# ProPrj_flap_controller_v2_2024-11-15.net
KiCad netlist of a schematic drawn in EasyEDA Pro
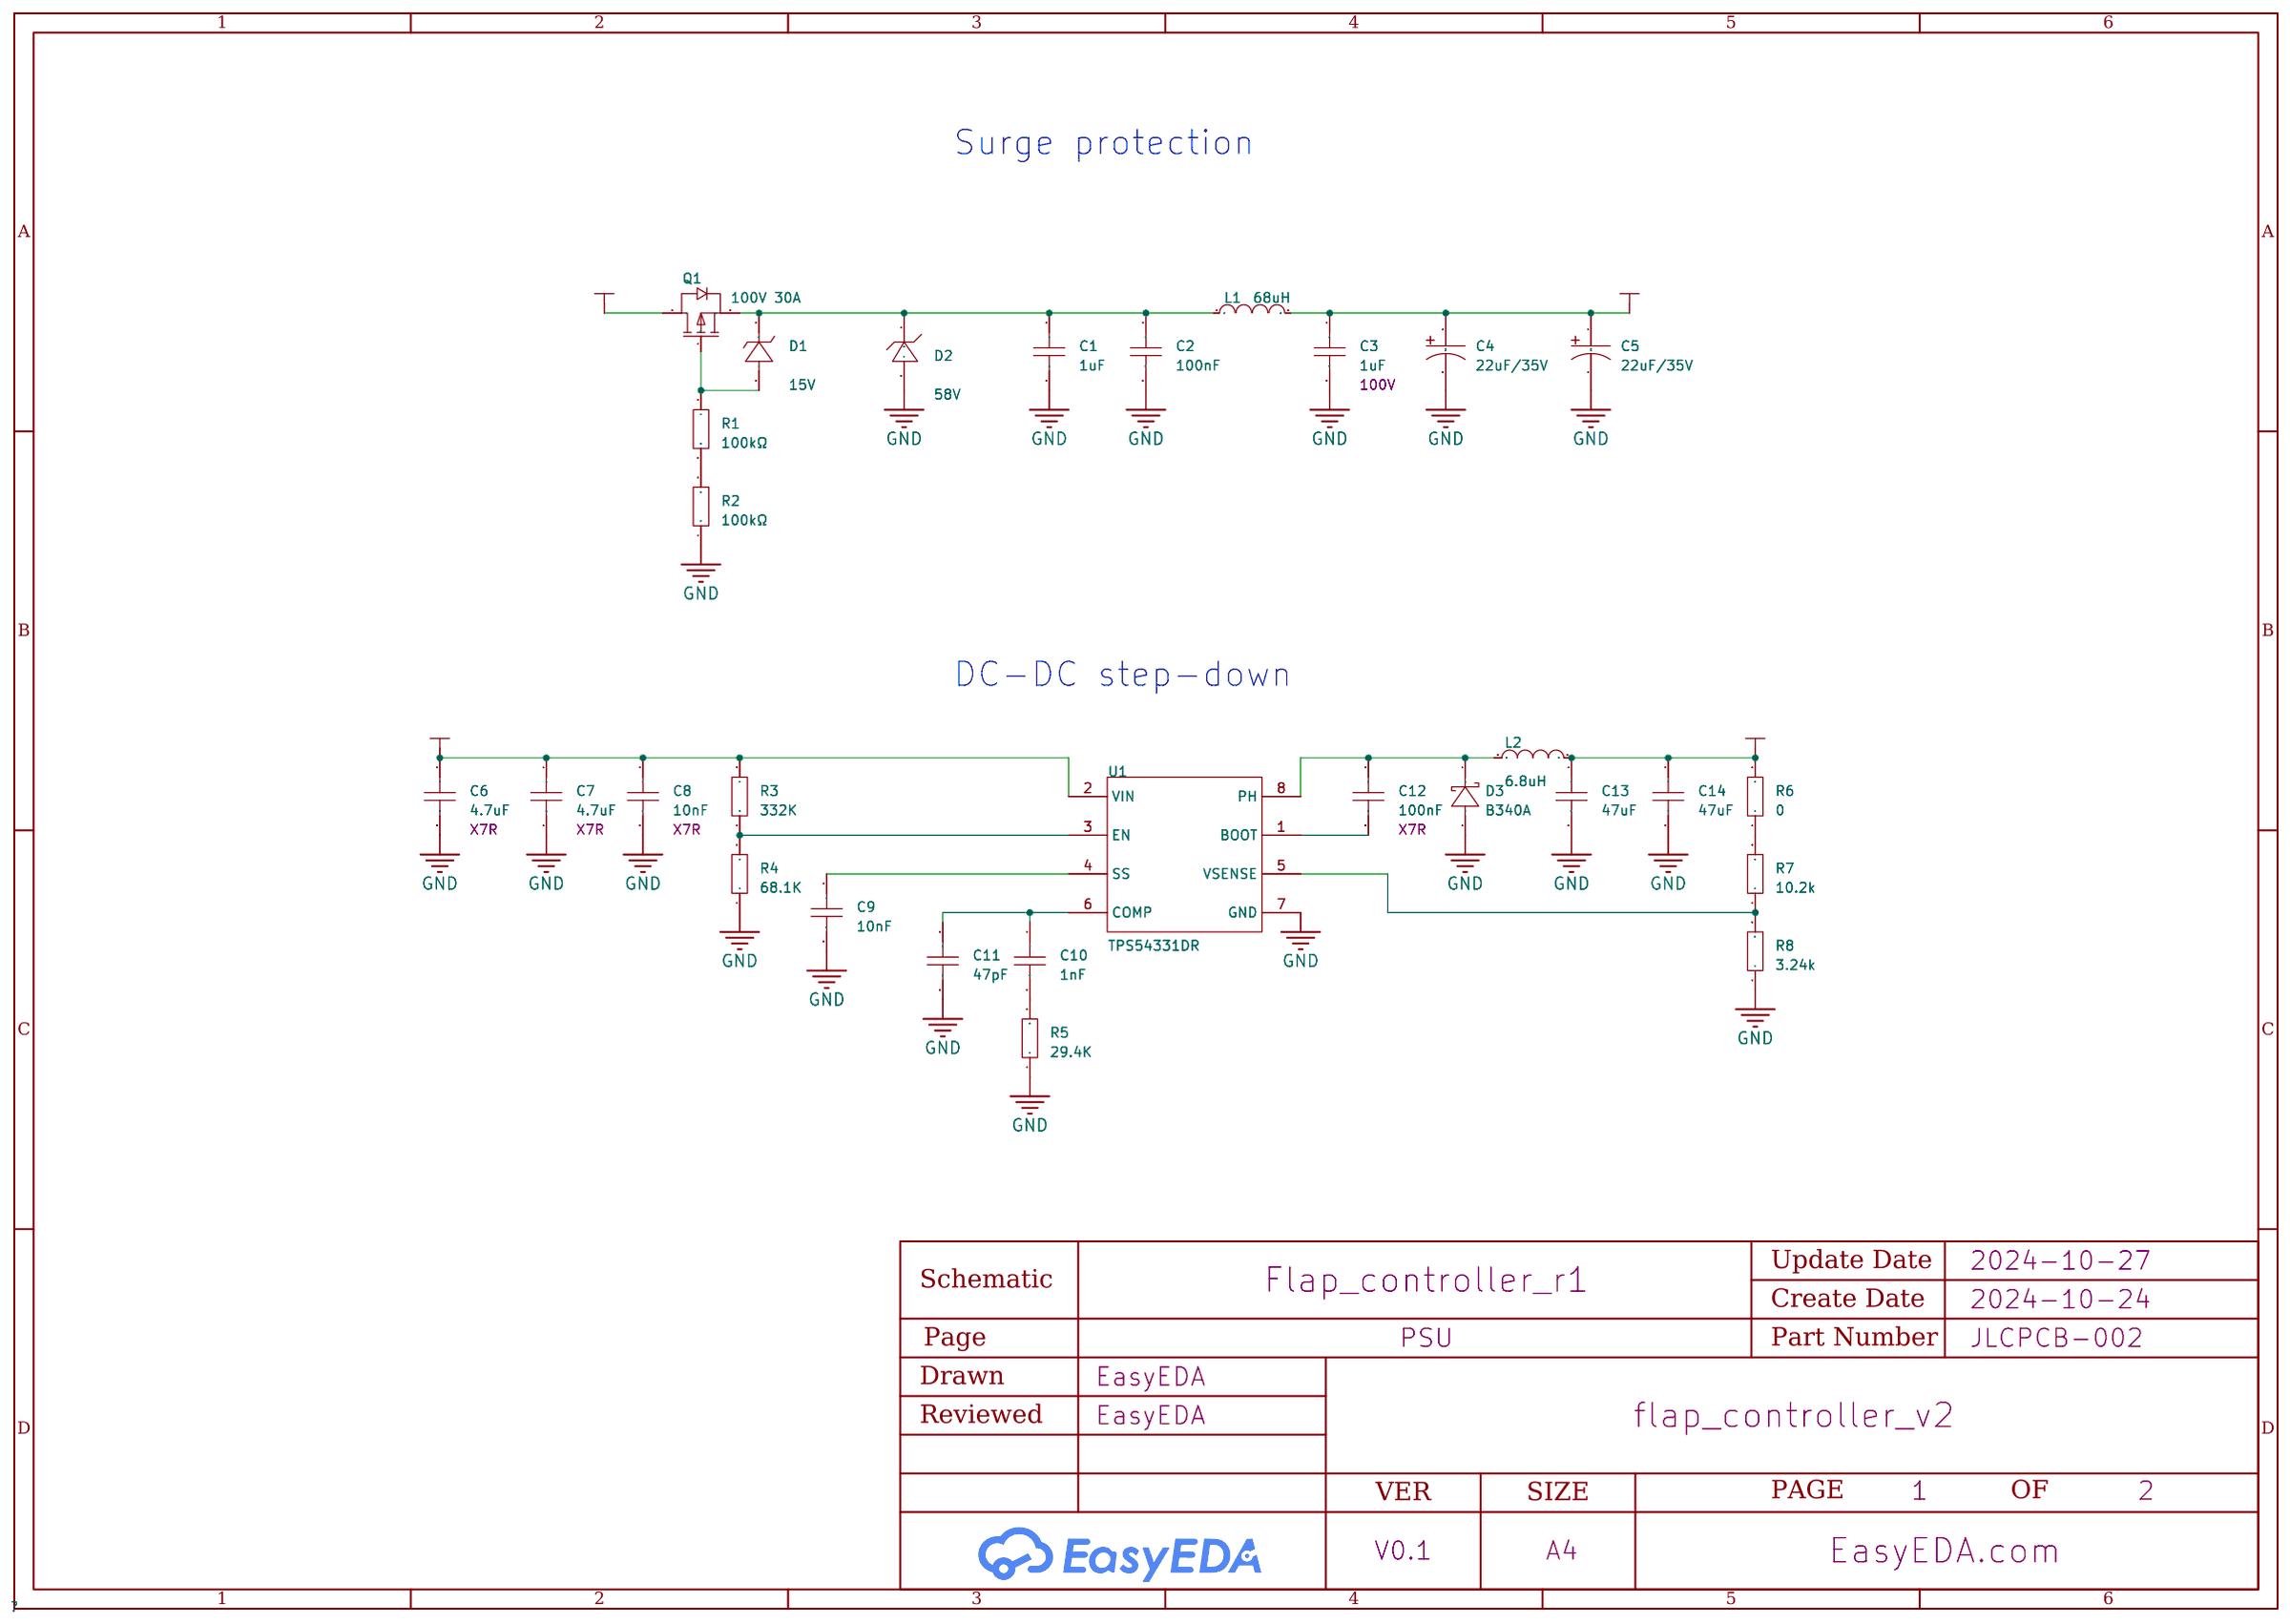
[diagram p0: PSU]
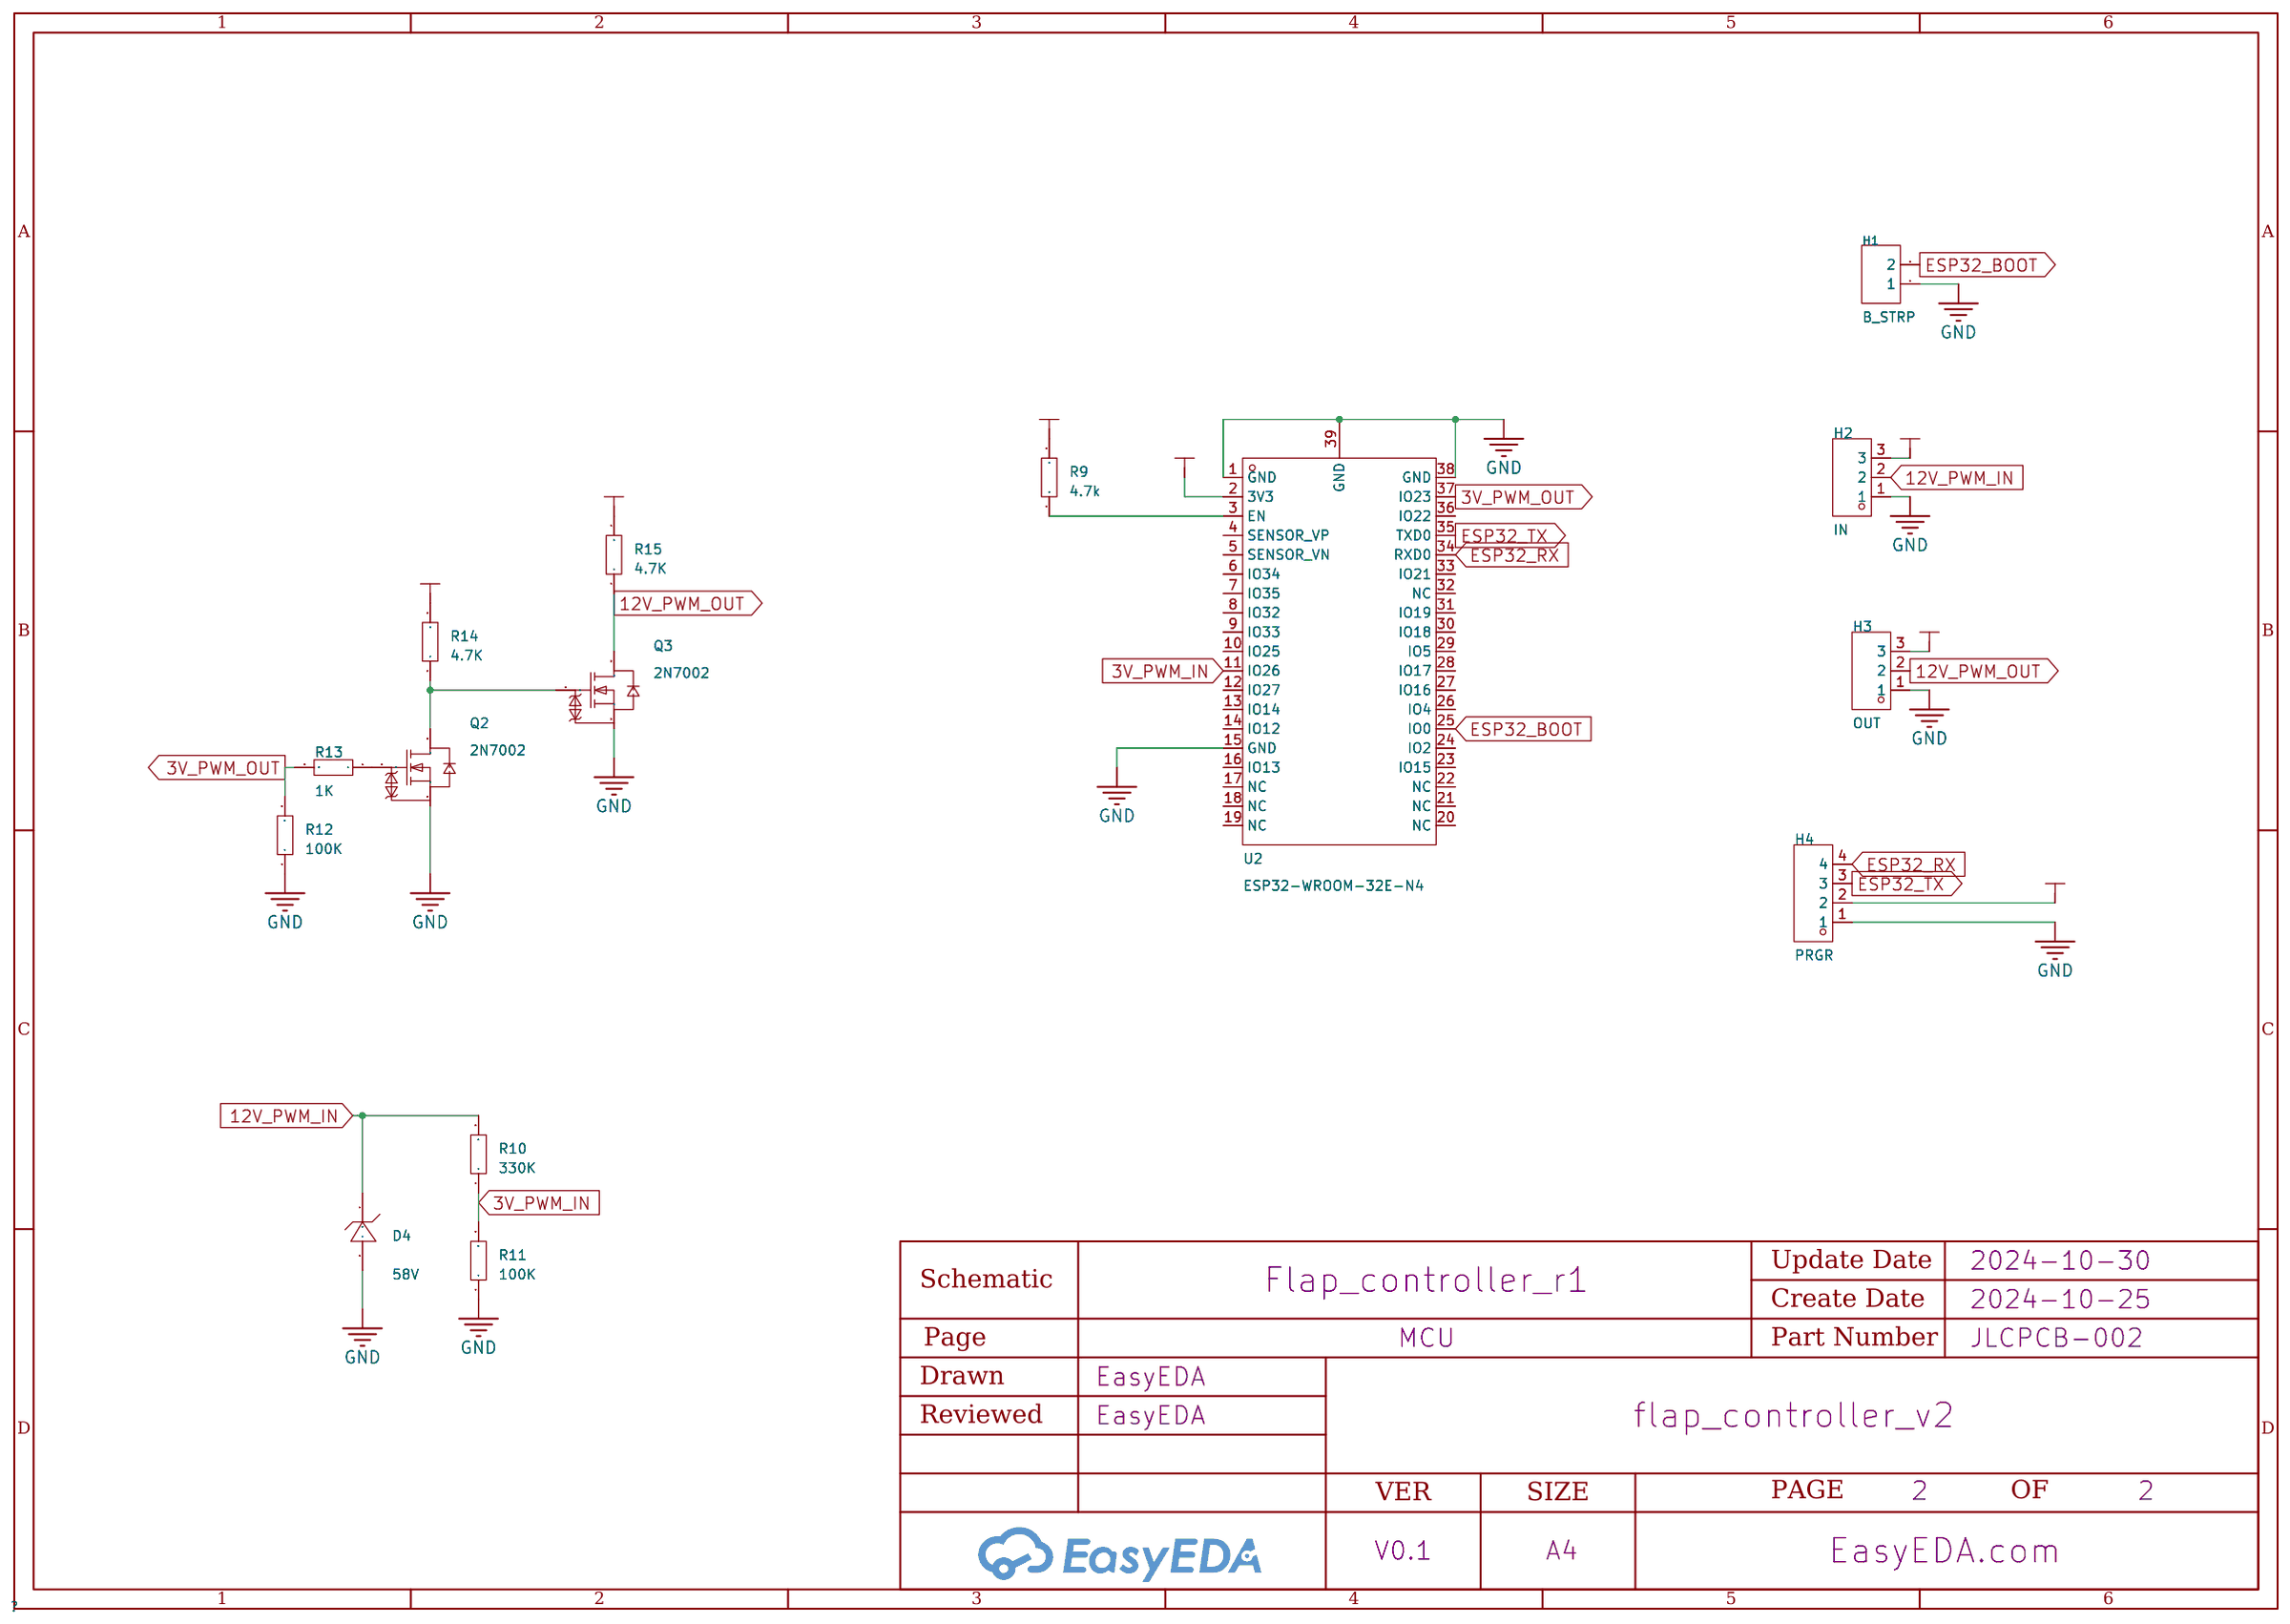
[diagram p1: MCU]

(export (version "E")
  (design (tool "Eeschema 10.0.6"))
  (components
    (comp (ref "C1")
      (value "1uF")
      (footprint "easyedapro:C0603")
      (fields (field (name "Manufacturer Part") "C0603X105K025T") (field (name "Manufacturer") "IHHEC(禾伸堂)"))
      (libsource (lib "easyedapro") (part "CAP"))
    )
    (comp (ref "C2")
      (value "100nF")
      (footprint "easyedapro:C0603")
      (fields (field (name "Manufacturer Part") "C0603X104K050T") (field (name "Manufacturer") "IHHEC(禾伸堂)"))
      (libsource (lib "easyedapro") (part "CAP"))
    )
    (comp (ref "C3")
      (value "1uF")
      (footprint "easyedapro:C0603")
      (fields (field (name "Voltage") "100V"))
      (libsource (lib "easyedapro") (part "CAP"))
    )
    (comp (ref "C4")
      (value "22uF/35V")
      (footprint "easyedapro:CAP-SMD_BD5.0-L5.3-W5.3-LS6.0-FD")
      (libsource (lib "easyedapro") (part "22UF/35V"))
    )
    (comp (ref "C5")
      (value "22uF/35V")
      (footprint "easyedapro:CAP-SMD_BD5.0-L5.3-W5.3-LS6.0-FD")
      (libsource (lib "easyedapro") (part "22UF/35V"))
    )
    (comp (ref "C6")
      (value "4.7uF")
      (footprint "easyedapro:C0603")
      (description "X7R")
      (libsource (lib "easyedapro") (part "CAP"))
    )
    (comp (ref "C7")
      (value "4.7uF")
      (footprint "easyedapro:C0603")
      (description "X7R")
      (libsource (lib "easyedapro") (part "CAP"))
    )
    (comp (ref "C8")
      (value "10nF")
      (footprint "easyedapro:C0603")
      (fields (field (name "Supplier Footprint") "X7R"))
      (libsource (lib "easyedapro") (part "CAP"))
    )
    (comp (ref "C9")
      (value "10nF")
      (footprint "easyedapro:C0603")
      (libsource (lib "easyedapro") (part "CAP"))
    )
    (comp (ref "C10")
      (value "1nF")
      (footprint "easyedapro:C0603")
      (libsource (lib "easyedapro") (part "CAP"))
    )
    (comp (ref "C11")
      (value "47pF")
      (footprint "easyedapro:C0603")
      (libsource (lib "easyedapro") (part "CAP"))
    )
    (comp (ref "C12")
      (value "100nF")
      (footprint "easyedapro:C0603")
      (description "X7R")
      (libsource (lib "easyedapro") (part "CAP"))
    )
    (comp (ref "C13")
      (value "47uF")
      (footprint "easyedapro:C0603")
      (libsource (lib "easyedapro") (part "CAP"))
    )
    (comp (ref "C14")
      (value "47uF")
      (footprint "easyedapro:C0603")
      (libsource (lib "easyedapro") (part "CAP"))
    )
    (comp (ref "D1")
      (value "15V")
      (footprint "easyedapro:SOD-323_L1.7-W1.3-LS2.5-RD")
      (fields (field (name "Manufacturer Part") "SOD-323"))
      (libsource (lib "easyedapro") (part "SOD-323_C9900016724"))
    )
    (comp (ref "D2")
      (value "58V")
      (footprint "easyedapro:SMB_L4.6-W3.6-LS5.3-RD")
      (fields (field (name "Manufacturer Part") "DO-214AA"))
      (libsource (lib "easyedapro") (part "DO-214AA"))
    )
    (comp (ref "D3")
      (value "B340A")
      (footprint "easyedapro:SMA_L4.3-W2.6-LS5.0-RD")
      (fields (field (name "Manufacturer") "FUXINSEMI(富芯森美)"))
      (libsource (lib "easyedapro") (part "B340A_C3018525"))
    )
    (comp (ref "L1")
      (value "68uH")
      (footprint "easyedapro:L0603")
      (fields (field (name "Manufacturer Part") "CY54-68UH") (field (name "Manufacturer") "SHOU HAN(首韩)"))
      (libsource (lib "easyedapro") (part "电感"))
    )
    (comp (ref "L2")
      (value "6.8uH")
      (footprint "easyedapro:IND-SMD_L4.5-W4.0")
      (fields (field (name "Manufacturer Part") "CY43-6.8UH") (field (name "Manufacturer") "SHOU HAN(首韩)"))
      (libsource (lib "easyedapro") (part "CY43-6.8UH"))
    )
    (comp (ref "Q1")
      (value "100V 30A")
      (footprint "easyedapro:TO-252-2_L6.6-W6.1-P4.57-LS10.1-BL")
      (fields (field (name "Manufacturer Part") "AP30P10D") (field (name "Manufacturer") "APM(永源微电子)"))
      (libsource (lib "easyedapro") (part "AP30P10D"))
    )
    (comp (ref "R1")
      (value "100kΩ")
      (footprint "easyedapro:R0603")
      (fields (field (name "Manufacturer Part") "SCR0603F100K") (field (name "Manufacturer") "VO(翔胜)"))
      (libsource (lib "easyedapro") (part "Res"))
    )
    (comp (ref "R2")
      (value "100kΩ")
      (footprint "easyedapro:R0603")
      (fields (field (name "Manufacturer Part") "SCR0603F100K") (field (name "Manufacturer") "VO(翔胜)"))
      (libsource (lib "easyedapro") (part "Res"))
    )
    (comp (ref "R3")
      (value "332K")
      (footprint "easyedapro:R0603")
      (libsource (lib "easyedapro") (part "Res"))
    )
    (comp (ref "R4")
      (value "68.1K")
      (footprint "easyedapro:R0603")
      (libsource (lib "easyedapro") (part "Res"))
    )
    (comp (ref "R5")
      (value "29.4K")
      (footprint "easyedapro:R0603")
      (libsource (lib "easyedapro") (part "Res"))
    )
    (comp (ref "R6") (value "0") (footprint "easyedapro:R0603") (libsource (lib "easyedapro") (part "Res")))
    (comp (ref "R7")
      (value "10.2k")
      (footprint "easyedapro:R0603")
      (libsource (lib "easyedapro") (part "Res"))
    )
    (comp (ref "R8")
      (value "3.24k")
      (footprint "easyedapro:R0603")
      (libsource (lib "easyedapro") (part "Res"))
    )
    (comp (ref "U1")
      (value "TPS54331DR")
      (footprint "easyedapro:SOIC-8_L5.0-W4.0-P1.27-LS6.0-BL")
      (fields (field (name "Manufacturer") "TI(德州仪器)"))
      (libsource (lib "easyedapro") (part "TPS54331DR"))
    )
    (comp (ref "D4")
      (value "58V")
      (footprint "easyedapro:SMB_L4.6-W3.6-LS5.3-RD")
      (fields (field (name "Manufacturer Part") "DO-214AA"))
      (libsource (lib "easyedapro") (part "DO-214AA"))
    )
    (comp (ref "H1")
      (value "B_STRP")
      (footprint "easyedapro:HDR-TH_2P-P2.54-V-F")
      (fields (field (name "Manufacturer Part") "B-2100S02P-A110") (field (name "Manufacturer") "Ckmtw(灿科盟)"))
      (libsource (lib "easyedapro") (part "Header-Female-2.54_1x2"))
    )
    (comp (ref "H2")
      (value "IN")
      (footprint "easyedapro:HDR-TH_3P-P2.00-V-M")
      (fields (field (name "Manufacturer Part") "3pin插件排针"))
      (libsource (lib "easyedapro") (part "3PIN插件排针"))
    )
    (comp (ref "H3")
      (value "OUT")
      (footprint "easyedapro:HDR-TH_3P-P2.00-V-M")
      (fields (field (name "Manufacturer Part") "3pin插件排针"))
      (libsource (lib "easyedapro") (part "3PIN插件排针"))
    )
    (comp (ref "H4")
      (value "PRGR")
      (footprint "easyedapro:HDR-TH_4P-P2.54-V-M")
      (fields (field (name "Manufacturer Part") "HDR2.54-LI-2x4P"))
      (libsource (lib "easyedapro") (part "HDR2.54-LI-2X4P"))
    )
    (comp (ref "Q2")
      (value "2N7002")
      (footprint "easyedapro:SOT-23-3_L3.0-W1.7-P0.95-LS2.9-BR")
      (fields (field (name "Manufacturer") "FOSAN(富信)"))
      (libsource (lib "easyedapro") (part "L2N7002SLLT1G"))
    )
    (comp (ref "Q3")
      (value "2N7002")
      (footprint "easyedapro:SOT-23-3_L3.0-W1.7-P0.95-LS2.9-BR")
      (fields (field (name "Manufacturer") "FOSAN(富信)"))
      (libsource (lib "easyedapro") (part "L2N7002SLLT1G"))
    )
    (comp (ref "R9")
      (value "4.7k")
      (footprint "easyedapro:R0603")
      (libsource (lib "easyedapro") (part "Res"))
    )
    (comp (ref "R10")
      (value "330K")
      (footprint "easyedapro:R0603")
      (libsource (lib "easyedapro") (part "Res"))
    )
    (comp (ref "R11")
      (value "100K")
      (footprint "easyedapro:R0603")
      (libsource (lib "easyedapro") (part "Res"))
    )
    (comp (ref "R12")
      (value "100K")
      (footprint "easyedapro:R0603")
      (libsource (lib "easyedapro") (part "Res"))
    )
    (comp (ref "R13") (value "1K") (footprint "easyedapro:R0603") (libsource (lib "easyedapro") (part "Res")))
    (comp (ref "R14")
      (value "4.7K")
      (footprint "easyedapro:R0603")
      (libsource (lib "easyedapro") (part "Res"))
    )
    (comp (ref "R15")
      (value "4.7K")
      (footprint "easyedapro:R0603")
      (libsource (lib "easyedapro") (part "Res"))
    )
    (comp (ref "U2")
      (value "ESP32-WROOM-32E-N4")
      (footprint "easyedapro:WIFI-SMD_ESP32-WROOM-32E")
      (fields (field (name "Manufacturer") "ESPRESSIF(乐鑫)"))
      (libsource (lib "easyedapro") (part "ESP32-WROOM-32E(4MB)"))
    )
  )
  (nets
    (net (code "1") (name "3V3") (class "Default")
      (node (ref "C13") (pin "1") (pinfunction "1_1") (pintype "input"))
      (node (ref "C14") (pin "1") (pinfunction "1_1") (pintype "input"))
      (node (ref "H4") (pin "2") (pinfunction "2_2") (pintype "unspecified"))
      (node (ref "L2") (pin "2") (pinfunction "2_2") (pintype "unspecified"))
      (node (ref "R6") (pin "2") (pinfunction "2_2") (pintype "input"))
      (node (ref "R9") (pin "2") (pinfunction "2_2") (pintype "input"))
      (node (ref "U2") (pin "2") (pinfunction "3V3_2") (pintype "unspecified"))
    )
    (net (code "2") (name "3V_PWM_IN") (class "Default")
      (node (ref "R10") (pin "1") (pinfunction "1_1") (pintype "input"))
      (node (ref "R11") (pin "2") (pinfunction "2_2") (pintype "input"))
      (node (ref "U2") (pin "11") (pinfunction "IO26_11") (pintype "unspecified"))
    )
    (net (code "3") (name "3V_PWM_OUT") (class "Default")
      (node (ref "R12") (pin "2") (pinfunction "2_2") (pintype "input"))
      (node (ref "R13") (pin "2") (pinfunction "2_2") (pintype "input"))
      (node (ref "U2") (pin "37") (pinfunction "IO23_37") (pintype "unspecified"))
    )
    (net (code "4") (name "12V") (class "Default")
      (node (ref "H2") (pin "3") (pinfunction "3_3") (pintype "unspecified"))
      (node (ref "H3") (pin "3") (pinfunction "3_3") (pintype "unspecified"))
      (node (ref "Q1") (pin "3") (pinfunction "D_3") (pintype "unspecified"))
    )
    (net (code "5") (name "12V_PWM_IN") (class "Default")
      (node (ref "D4") (pin "1") (pinfunction "C_1") (pintype "unspecified"))
      (node (ref "H2") (pin "2") (pinfunction "2_2") (pintype "unspecified"))
      (node (ref "R10") (pin "2") (pinfunction "2_2") (pintype "input"))
    )
    (net (code "6") (name "12V_PWM_OUT") (class "Default")
      (node (ref "H3") (pin "2") (pinfunction "2_2") (pintype "unspecified"))
      (node (ref "Q3") (pin "3") (pinfunction "D_3") (pintype "unspecified"))
      (node (ref "R15") (pin "1") (pinfunction "1_1") (pintype "input"))
    )
    (net (code "7") (name "12V_S") (class "Default")
      (node (ref "C3") (pin "1") (pinfunction "1_1") (pintype "input"))
      (node (ref "C4") (pin "1") (pinfunction "1_1") (pintype "unspecified"))
      (node (ref "C5") (pin "1") (pinfunction "1_1") (pintype "unspecified"))
      (node (ref "C6") (pin "1") (pinfunction "1_1") (pintype "input"))
      (node (ref "C7") (pin "1") (pinfunction "1_1") (pintype "input"))
      (node (ref "C8") (pin "1") (pinfunction "1_1") (pintype "input"))
      (node (ref "L1") (pin "2") (pinfunction "2_2") (pintype "input"))
      (node (ref "R14") (pin "2") (pinfunction "2_2") (pintype "input"))
      (node (ref "R15") (pin "2") (pinfunction "2_2") (pintype "input"))
      (node (ref "R3") (pin "2") (pinfunction "2_2") (pintype "input"))
      (node (ref "U1") (pin "2") (pinfunction "VIN_2") (pintype "unspecified"))
    )
    (net (code "8") (name "ESP32_BOOT") (class "Default")
      (node (ref "H1") (pin "2") (pinfunction "2_2") (pintype "input"))
      (node (ref "U2") (pin "25") (pinfunction "IO0_25") (pintype "unspecified"))
    )
    (net (code "9") (name "ESP32_RX") (class "Default")
      (node (ref "H4") (pin "4") (pinfunction "4_4") (pintype "unspecified"))
      (node (ref "U2") (pin "34") (pinfunction "RXD0_34") (pintype "unspecified"))
    )
    (net (code "10") (name "ESP32_TX") (class "Default")
      (node (ref "H4") (pin "3") (pinfunction "3_3") (pintype "unspecified"))
      (node (ref "U2") (pin "35") (pinfunction "TXD0_35") (pintype "unspecified"))
    )
    (net (code "11") (name "GND") (class "Default")
      (node (ref "C1") (pin "2") (pinfunction "2_2") (pintype "input"))
      (node (ref "C11") (pin "2") (pinfunction "2_2") (pintype "input"))
      (node (ref "C13") (pin "2") (pinfunction "2_2") (pintype "input"))
      (node (ref "C14") (pin "2") (pinfunction "2_2") (pintype "input"))
      (node (ref "C2") (pin "2") (pinfunction "2_2") (pintype "input"))
      (node (ref "C3") (pin "2") (pinfunction "2_2") (pintype "input"))
      (node (ref "C4") (pin "2") (pinfunction "2_2") (pintype "unspecified"))
      (node (ref "C5") (pin "2") (pinfunction "2_2") (pintype "unspecified"))
      (node (ref "C6") (pin "2") (pinfunction "2_2") (pintype "input"))
      (node (ref "C7") (pin "2") (pinfunction "2_2") (pintype "input"))
      (node (ref "C8") (pin "2") (pinfunction "2_2") (pintype "input"))
      (node (ref "C9") (pin "2") (pinfunction "2_2") (pintype "input"))
      (node (ref "D2") (pin "2") (pinfunction "A_2") (pintype "unspecified"))
      (node (ref "D3") (pin "2") (pinfunction "A_2") (pintype "unspecified"))
      (node (ref "D4") (pin "2") (pinfunction "A_2") (pintype "unspecified"))
      (node (ref "H1") (pin "1") (pinfunction "1_1") (pintype "input"))
      (node (ref "H2") (pin "1") (pinfunction "1_1") (pintype "unspecified"))
      (node (ref "H3") (pin "1") (pinfunction "1_1") (pintype "unspecified"))
      (node (ref "H4") (pin "1") (pinfunction "1_1") (pintype "unspecified"))
      (node (ref "Q2") (pin "2") (pinfunction "S_2") (pintype "unspecified"))
      (node (ref "Q3") (pin "2") (pinfunction "S_2") (pintype "unspecified"))
      (node (ref "R11") (pin "1") (pinfunction "1_1") (pintype "input"))
      (node (ref "R12") (pin "1") (pinfunction "1_1") (pintype "input"))
      (node (ref "R2") (pin "1") (pinfunction "1_1") (pintype "input"))
      (node (ref "R4") (pin "1") (pinfunction "1_1") (pintype "input"))
      (node (ref "R5") (pin "1") (pinfunction "1_1") (pintype "input"))
      (node (ref "R8") (pin "1") (pinfunction "1_1") (pintype "input"))
      (node (ref "U1") (pin "7") (pinfunction "GND_7") (pintype "unspecified"))
      (node (ref "U2") (pin "1") (pinfunction "GND_1") (pintype "unspecified"))
      (node (ref "U2") (pin "15") (pinfunction "GND_15") (pintype "unspecified"))
      (node (ref "U2") (pin "38") (pinfunction "GND_38") (pintype "unspecified"))
      (node (ref "U2") (pin "39") (pinfunction "GND_39") (pintype "unspecified"))
    )
    (net (code "12") (name "Net-(C10-Pad2)") (class "Default")
      (node (ref "C10") (pin "2") (pinfunction "2_2") (pintype "input"))
      (node (ref "R5") (pin "2") (pinfunction "2_2") (pintype "input"))
    )
    (net (code "13") (name "Net-(D1-A)") (class "Default")
      (node (ref "D1") (pin "2") (pinfunction "A_2") (pintype "unspecified"))
      (node (ref "Q1") (pin "1") (pinfunction "G_1") (pintype "unspecified"))
      (node (ref "R1") (pin "1") (pinfunction "1_1") (pintype "input"))
    )
    (net (code "14") (name "Net-(D1-K)") (class "Default")
      (node (ref "C1") (pin "1") (pinfunction "1_1") (pintype "input"))
      (node (ref "C2") (pin "1") (pinfunction "1_1") (pintype "input"))
      (node (ref "D1") (pin "1") (pinfunction "K_1") (pintype "unspecified"))
      (node (ref "D2") (pin "1") (pinfunction "C_1") (pintype "unspecified"))
      (node (ref "L1") (pin "1") (pinfunction "1_1") (pintype "input"))
      (node (ref "Q1") (pin "2") (pinfunction "S_2") (pintype "unspecified"))
    )
    (net (code "15") (name "Net-(D3-K)") (class "Default")
      (node (ref "C12") (pin "1") (pinfunction "1_1") (pintype "input"))
      (node (ref "D3") (pin "1") (pinfunction "K_1") (pintype "unspecified"))
      (node (ref "L2") (pin "1") (pinfunction "1_1") (pintype "unspecified"))
      (node (ref "U1") (pin "8") (pinfunction "PH_8") (pintype "unspecified"))
    )
    (net (code "16") (name "Net-(Q2-D)") (class "Default")
      (node (ref "Q2") (pin "3") (pinfunction "D_3") (pintype "unspecified"))
      (node (ref "Q3") (pin "1") (pinfunction "G_1") (pintype "unspecified"))
      (node (ref "R14") (pin "1") (pinfunction "1_1") (pintype "input"))
    )
    (net (code "17") (name "Net-(Q2-G)") (class "Default")
      (node (ref "Q2") (pin "1") (pinfunction "G_1") (pintype "unspecified"))
      (node (ref "R13") (pin "1") (pinfunction "1_1") (pintype "input"))
    )
    (net (code "18") (name "Net-(R1-Pad2)") (class "Default")
      (node (ref "R1") (pin "2") (pinfunction "2_2") (pintype "input"))
      (node (ref "R2") (pin "2") (pinfunction "2_2") (pintype "input"))
    )
    (net (code "19") (name "Net-(R6-Pad1)") (class "Default")
      (node (ref "R6") (pin "1") (pinfunction "1_1") (pintype "input"))
      (node (ref "R7") (pin "2") (pinfunction "2_2") (pintype "input"))
    )
    (net (code "20") (name "Net-(U1-BOOT)") (class "Default")
      (node (ref "C12") (pin "2") (pinfunction "2_2") (pintype "input"))
      (node (ref "U1") (pin "1") (pinfunction "BOOT_1") (pintype "unspecified"))
    )
    (net (code "21") (name "Net-(U1-COMP)") (class "Default")
      (node (ref "C10") (pin "1") (pinfunction "1_1") (pintype "input"))
      (node (ref "C11") (pin "1") (pinfunction "1_1") (pintype "input"))
      (node (ref "U1") (pin "6") (pinfunction "COMP_6") (pintype "unspecified"))
    )
    (net (code "22") (name "Net-(U1-EN)") (class "Default")
      (node (ref "R3") (pin "1") (pinfunction "1_1") (pintype "input"))
      (node (ref "R4") (pin "2") (pinfunction "2_2") (pintype "input"))
      (node (ref "U1") (pin "3") (pinfunction "EN_3") (pintype "unspecified"))
    )
    (net (code "23") (name "Net-(U1-SS)") (class "Default")
      (node (ref "C9") (pin "1") (pinfunction "1_1") (pintype "input"))
      (node (ref "U1") (pin "4") (pinfunction "SS_4") (pintype "unspecified"))
    )
    (net (code "24") (name "Net-(U1-VSENSE)") (class "Default")
      (node (ref "R7") (pin "1") (pinfunction "1_1") (pintype "input"))
      (node (ref "R8") (pin "2") (pinfunction "2_2") (pintype "input"))
      (node (ref "U1") (pin "5") (pinfunction "VSENSE_5") (pintype "unspecified"))
    )
    (net (code "25") (name "Net-(U2-EN)") (class "Default")
      (node (ref "R9") (pin "1") (pinfunction "1_1") (pintype "input"))
      (node (ref "U2") (pin "3") (pinfunction "EN_3") (pintype "unspecified"))
    )
    (net (code "26") (name "unconnected-(U2-IO2-Pad24)") (class "Default")
      (node (ref "U2") (pin "24") (pinfunction "IO2_24") (pintype "unspecified"))
    )
    (net (code "27") (name "unconnected-(U2-IO4-Pad26)") (class "Default")
      (node (ref "U2") (pin "26") (pinfunction "IO4_26") (pintype "unspecified"))
    )
    (net (code "28") (name "unconnected-(U2-IO5-Pad29)") (class "Default")
      (node (ref "U2") (pin "29") (pinfunction "IO5_29") (pintype "unspecified"))
    )
    (net (code "29") (name "unconnected-(U2-IO12-Pad14)") (class "Default")
      (node (ref "U2") (pin "14") (pinfunction "IO12_14") (pintype "unspecified"))
    )
    (net (code "30") (name "unconnected-(U2-IO13-Pad16)") (class "Default")
      (node (ref "U2") (pin "16") (pinfunction "IO13_16") (pintype "unspecified"))
    )
    (net (code "31") (name "unconnected-(U2-IO14-Pad13)") (class "Default")
      (node (ref "U2") (pin "13") (pinfunction "IO14_13") (pintype "unspecified"))
    )
    (net (code "32") (name "unconnected-(U2-IO15-Pad23)") (class "Default")
      (node (ref "U2") (pin "23") (pinfunction "IO15_23") (pintype "unspecified"))
    )
    (net (code "33") (name "unconnected-(U2-IO16-Pad27)") (class "Default")
      (node (ref "U2") (pin "27") (pinfunction "IO16_27") (pintype "unspecified"))
    )
    (net (code "34") (name "unconnected-(U2-IO17-Pad28)") (class "Default")
      (node (ref "U2") (pin "28") (pinfunction "IO17_28") (pintype "unspecified"))
    )
    (net (code "35") (name "unconnected-(U2-IO18-Pad30)") (class "Default")
      (node (ref "U2") (pin "30") (pinfunction "IO18_30") (pintype "unspecified"))
    )
    (net (code "36") (name "unconnected-(U2-IO19-Pad31)") (class "Default")
      (node (ref "U2") (pin "31") (pinfunction "IO19_31") (pintype "unspecified"))
    )
    (net (code "37") (name "unconnected-(U2-IO21-Pad33)") (class "Default")
      (node (ref "U2") (pin "33") (pinfunction "IO21_33") (pintype "unspecified"))
    )
    (net (code "38") (name "unconnected-(U2-IO22-Pad36)") (class "Default")
      (node (ref "U2") (pin "36") (pinfunction "IO22_36") (pintype "unspecified"))
    )
    (net (code "39") (name "unconnected-(U2-IO25-Pad10)") (class "Default")
      (node (ref "U2") (pin "10") (pinfunction "IO25_10") (pintype "unspecified"))
    )
    (net (code "40") (name "unconnected-(U2-IO27-Pad12)") (class "Default")
      (node (ref "U2") (pin "12") (pinfunction "IO27_12") (pintype "unspecified"))
    )
    (net (code "41") (name "unconnected-(U2-IO32-Pad8)") (class "Default")
      (node (ref "U2") (pin "8") (pinfunction "IO32_8") (pintype "unspecified"))
    )
    (net (code "42") (name "unconnected-(U2-IO33-Pad9)") (class "Default")
      (node (ref "U2") (pin "9") (pinfunction "IO33_9") (pintype "unspecified"))
    )
    (net (code "43") (name "unconnected-(U2-IO34-Pad6)") (class "Default")
      (node (ref "U2") (pin "6") (pinfunction "IO34_6") (pintype "unspecified"))
    )
    (net (code "44") (name "unconnected-(U2-IO35-Pad7)") (class "Default")
      (node (ref "U2") (pin "7") (pinfunction "IO35_7") (pintype "unspecified"))
    )
    (net (code "45") (name "unconnected-(U2-NC-Pad17)") (class "Default")
      (node (ref "U2") (pin "17") (pinfunction "NC_17") (pintype "unspecified"))
    )
    (net (code "46") (name "unconnected-(U2-NC-Pad18)") (class "Default")
      (node (ref "U2") (pin "18") (pinfunction "NC_18") (pintype "unspecified"))
    )
    (net (code "47") (name "unconnected-(U2-NC-Pad19)") (class "Default")
      (node (ref "U2") (pin "19") (pinfunction "NC_19") (pintype "unspecified"))
    )
    (net (code "48") (name "unconnected-(U2-NC-Pad20)") (class "Default")
      (node (ref "U2") (pin "20") (pinfunction "NC_20") (pintype "unspecified"))
    )
    (net (code "49") (name "unconnected-(U2-NC-Pad21)") (class "Default")
      (node (ref "U2") (pin "21") (pinfunction "NC_21") (pintype "unspecified"))
    )
    (net (code "50") (name "unconnected-(U2-NC-Pad22)") (class "Default")
      (node (ref "U2") (pin "22") (pinfunction "NC_22") (pintype "unspecified"))
    )
    (net (code "51") (name "unconnected-(U2-NC-Pad32)") (class "Default")
      (node (ref "U2") (pin "32") (pinfunction "NC_32") (pintype "unspecified"))
    )
    (net (code "52") (name "unconnected-(U2-SENSOR_VN-Pad5)") (class "Default")
      (node (ref "U2") (pin "5") (pinfunction "SENSOR_VN_5") (pintype "unspecified"))
    )
    (net (code "53") (name "unconnected-(U2-SENSOR_VP-Pad4)") (class "Default")
      (node (ref "U2") (pin "4") (pinfunction "SENSOR_VP_4") (pintype "unspecified"))
    )
  )
)
